# powerAndCommunication.net
KiCad netlist of a schematic drawn in Altium Designer
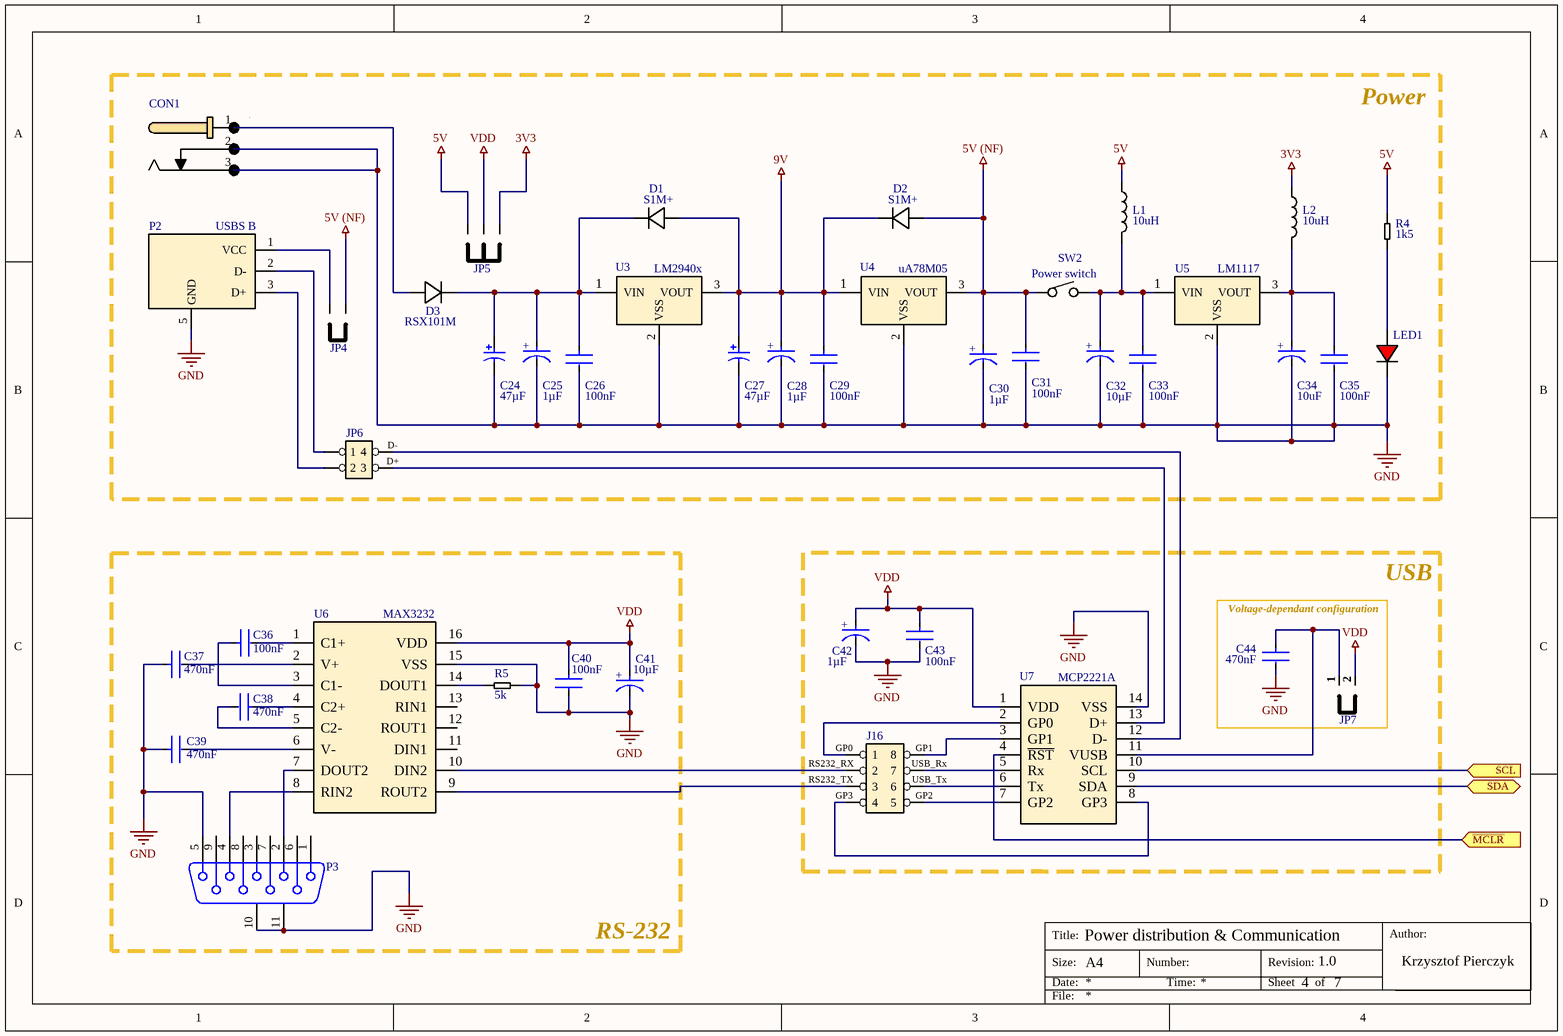
[diagram p0: powerAndCommunication.SchDoc]

(export (version "E")
  (design (tool "Eeschema 10.0.6"))
  (components
    (comp (ref "C24")
      (value "EEE-FK1V331P")
      (footprint "PNSC-EEE-FK1V331P_L")
      (description "Aluminum Electrolytic Capacitor, 330 uF, 35 V, -55 to 105 degC, 2-Pin CAPAE, RoHS, Tape and Reel")
      (fields (field (name "CAPACITANCE") "47µF") (field (name "MANUFACTURER") "Panasonic"))
      (libsource (lib "Altium Content Vault") (part "CAP-P-2"))
    )
    (comp (ref "C25")
      (value "F981C106MSAAS1")
      (footprint "FP-F98S-MFG")
      (description "CAP TANT 10UF 20% 16V 0805")
      (fields
        (field (name "TOLERANCE") "20%")
        (field (name "CAPACITANCE") "1µF")
        (field (name "OCTOPART") "https://octopart.com/f981c106msaas1-avx-49645945")
      )
      (libsource (lib "Altium Content Vault") (part "cf48714ba7e38822c1575c7ec0b6d1f"))
    )
    (comp (ref "C26")
      (value "100nF")
      (footprint "FP-C0805C-DN-MFG")
      (description "CAP CER 1000PF 50V C0G/NP0 0805")
      (fields
        (field (name "MANUFACTURER") "KEMET")
        (field (name "OCTOPART") "https://octopart.com/c0805c102j5gactu-kemet-97757")
      )
      (libsource (lib "Altium Content Vault") (part "b4654b650e69147ec39a6b967a45e02"))
    )
    (comp (ref "C27")
      (value "EEE-FK1V331P")
      (footprint "PNSC-EEE-FK1V331P_L")
      (description "Aluminum Electrolytic Capacitor, 330 uF, 35 V, -55 to 105 degC, 2-Pin CAPAE, RoHS, Tape and Reel")
      (fields (field (name "CAPACITANCE") "47µF") (field (name "MANUFACTURER") "Panasonic"))
      (libsource (lib "Altium Content Vault") (part "CAP-P-2"))
    )
    (comp (ref "C28")
      (value "F981C106MSAAS1")
      (footprint "FP-F98S-MFG")
      (description "CAP TANT 10UF 20% 16V 0805")
      (fields
        (field (name "TOLERANCE") "20%")
        (field (name "CAPACITANCE") "1µF")
        (field (name "OCTOPART") "https://octopart.com/f981c106msaas1-avx-49645945")
      )
      (libsource (lib "Altium Content Vault") (part "cf48714ba7e38822c1575c7ec0b6d1f"))
    )
    (comp (ref "C29")
      (value "100nF")
      (footprint "FP-C0805C-DN-MFG")
      (description "CAP CER 1000PF 50V C0G/NP0 0805")
      (fields
        (field (name "MANUFACTURER") "KEMET")
        (field (name "OCTOPART") "https://octopart.com/c0805c102j5gactu-kemet-97757")
      )
      (libsource (lib "Altium Content Vault") (part "b4654b650e69147ec39a6b967a45e02"))
    )
    (comp (ref "C30")
      (value "F981C106MSAAS1")
      (footprint "FP-F98S-MFG")
      (description "CAP TANT 10UF 20% 16V 0805")
      (fields
        (field (name "TOLERANCE") "20%")
        (field (name "CAPACITANCE") "1µF")
        (field (name "OCTOPART") "https://octopart.com/f981c106msaas1-avx-49645945")
      )
      (libsource (lib "Altium Content Vault") (part "cf48714ba7e38822c1575c7ec0b6d1f"))
    )
    (comp (ref "C31")
      (value "100nF")
      (footprint "FP-C0805C-DN-MFG")
      (description "CAP CER 1000PF 50V C0G/NP0 0805")
      (fields
        (field (name "MANUFACTURER") "KEMET")
        (field (name "OCTOPART") "https://octopart.com/c0805c102j5gactu-kemet-97757")
      )
      (libsource (lib "Altium Content Vault") (part "b4654b650e69147ec39a6b967a45e02"))
    )
    (comp (ref "C32")
      (value "F981C106MSAAS1")
      (footprint "FP-F98S-MFG")
      (description "CAP TANT 10UF 20% 16V 0805")
      (fields
        (field (name "TOLERANCE") "20%")
        (field (name "CAPACITANCE") "10µF")
        (field (name "OCTOPART") "https://octopart.com/f981c106msaas1-avx-49645945")
      )
      (libsource (lib "Altium Content Vault") (part "cf48714ba7e38822c1575c7ec0b6d1f"))
    )
    (comp (ref "C33")
      (value "100nF")
      (footprint "FP-C0805C-DN-MFG")
      (description "CAP CER 1000PF 50V C0G/NP0 0805")
      (fields
        (field (name "MANUFACTURER") "KEMET")
        (field (name "OCTOPART") "https://octopart.com/c0805c102j5gactu-kemet-97757")
      )
      (libsource (lib "Altium Content Vault") (part "b4654b650e69147ec39a6b967a45e02"))
    )
    (comp (ref "C34")
      (value "F981C106MSAAS1")
      (footprint "FP-F98S-MFG")
      (description "CAP TANT 10UF 20% 16V 0805")
      (fields
        (field (name "TOLERANCE") "20%")
        (field (name "CAPACITANCE") "10uF")
        (field (name "OCTOPART") "https://octopart.com/f981c106msaas1-avx-49645945")
      )
      (libsource (lib "Altium Content Vault") (part "cf48714ba7e38822c1575c7ec0b6d1f"))
    )
    (comp (ref "C35")
      (value "100nF")
      (footprint "FP-C0805C-DN-MFG")
      (description "CAP CER 1000PF 50V C0G/NP0 0805")
      (fields
        (field (name "MANUFACTURER") "KEMET")
        (field (name "OCTOPART") "https://octopart.com/c0805c102j5gactu-kemet-97757")
      )
      (libsource (lib "Altium Content Vault") (part "b4654b650e69147ec39a6b967a45e02"))
    )
    (comp (ref "C36")
      (value "100nF")
      (footprint "FP-C0805C-DN-MFG")
      (description "CAP CER 1000PF 50V C0G/NP0 0805")
      (fields
        (field (name "MANUFACTURER") "KEMET")
        (field (name "OCTOPART") "https://octopart.com/c0805c102j5gactu-kemet-97757")
      )
      (libsource (lib "Altium Content Vault") (part "b4654b650e69147ec39a6b967a45e02"))
    )
    (comp (ref "C37")
      (value "470nF")
      (footprint "FP-C0805C-DN-MFG")
      (description "CAP CER 1000PF 50V C0G/NP0 0805")
      (fields
        (field (name "MANUFACTURER") "KEMET")
        (field (name "OCTOPART") "https://octopart.com/c0805c102j5gactu-kemet-97757")
      )
      (libsource (lib "Altium Content Vault") (part "b4654b650e69147ec39a6b967a45e02"))
    )
    (comp (ref "C38")
      (value "470nF")
      (footprint "FP-C0805C-DN-MFG")
      (description "CAP CER 1000PF 50V C0G/NP0 0805")
      (fields
        (field (name "MANUFACTURER") "KEMET")
        (field (name "OCTOPART") "https://octopart.com/c0805c102j5gactu-kemet-97757")
      )
      (libsource (lib "Altium Content Vault") (part "b4654b650e69147ec39a6b967a45e02"))
    )
    (comp (ref "C39")
      (value "470nF")
      (footprint "FP-C0805C-DN-MFG")
      (description "CAP CER 1000PF 50V C0G/NP0 0805")
      (fields
        (field (name "MANUFACTURER") "KEMET")
        (field (name "OCTOPART") "https://octopart.com/c0805c102j5gactu-kemet-97757")
      )
      (libsource (lib "Altium Content Vault") (part "b4654b650e69147ec39a6b967a45e02"))
    )
    (comp (ref "C40")
      (value "100nF")
      (footprint "FP-C0805C-DN-MFG")
      (description "CAP CER 1000PF 50V C0G/NP0 0805")
      (fields
        (field (name "MANUFACTURER") "KEMET")
        (field (name "OCTOPART") "https://octopart.com/c0805c102j5gactu-kemet-97757")
      )
      (libsource (lib "Altium Content Vault") (part "b4654b650e69147ec39a6b967a45e02"))
    )
    (comp (ref "C41")
      (value "F981C106MSAAS1")
      (footprint "FP-F98S-MFG")
      (description "CAP TANT 10UF 20% 16V 0805")
      (fields
        (field (name "TOLERANCE") "20%")
        (field (name "CAPACITANCE") "10µF")
        (field (name "OCTOPART") "https://octopart.com/f981c106msaas1-avx-49645945")
      )
      (libsource (lib "Altium Content Vault") (part "cf48714ba7e38822c1575c7ec0b6d1f"))
    )
    (comp (ref "C42")
      (value "F981C106MSAAS1")
      (footprint "FP-F98S-MFG")
      (description "CAP TANT 10UF 20% 16V 0805")
      (fields
        (field (name "TOLERANCE") "20%")
        (field (name "CAPACITANCE") "1µF")
        (field (name "OCTOPART") "https://octopart.com/f981c106msaas1-avx-49645945")
      )
      (libsource (lib "Altium Content Vault") (part "cf48714ba7e38822c1575c7ec0b6d1f"))
    )
    (comp (ref "C43")
      (value "100nF")
      (footprint "FP-C0805C-DN-MFG")
      (description "CAP CER 1000PF 50V C0G/NP0 0805")
      (fields
        (field (name "MANUFACTURER") "KEMET")
        (field (name "OCTOPART") "https://octopart.com/c0805c102j5gactu-kemet-97757")
      )
      (libsource (lib "Altium Content Vault") (part "b4654b650e69147ec39a6b967a45e02"))
    )
    (comp (ref "C44")
      (value "470nF")
      (footprint "FP-C0805C-DN-MFG")
      (description "CAP CER 1000PF 50V C0G/NP0 0805")
      (fields
        (field (name "MANUFACTURER") "KEMET")
        (field (name "OCTOPART") "https://octopart.com/c0805c102j5gactu-kemet-97757")
      )
      (libsource (lib "Altium Content Vault") (part "b4654b650e69147ec39a6b967a45e02"))
    )
    (comp (ref "CON1")
      (value "FC681477")
      (footprint "FC681477")
      (libsource (lib "miscellanea") (part "DC Jack"))
    )
    (comp (ref "D1")
      (value "S1M+")
      (footprint "SMA")
      (libsource (lib "discrete_semiconductors") (part "S1M+_1"))
    )
    (comp (ref "D2")
      (value "S1M+")
      (footprint "SMA")
      (libsource (lib "discrete_semiconductors") (part "S1M+_1"))
    )
    (comp (ref "D3")
      (value "RSX101M")
      (footprint "SOD-123")
      (libsource (lib "discrete_semiconductors") (part "RSX101M-30TR"))
    )
    (comp (ref "J16")
      (value "Header 2x4")
      (footprint "Header 2x4")
      (libsource (lib "goldpin") (part "Header 2x4"))
    )
    (comp (ref "JP4") (value "JUMPER-2") (footprint "HDR1X2") (libsource (lib "goldpin") (part "JUMPER-2")))
    (comp (ref "JP5") (value "JUMPER-3") (footprint "HDR1X3") (libsource (lib "goldpin") (part "JUMPER-3")))
    (comp (ref "JP6")
      (value "Header 2x2")
      (footprint "Header 2x2")
      (libsource (lib "goldpin") (part "Header 2x2"))
    )
    (comp (ref "JP7") (value "JUMPER-2") (footprint "Header 1x2") (libsource (lib "") (part "JUMPER-2_1")))
    (comp (ref "L1")
      (value "NL05JTC100")
      (footprint "0805")
      (description "SMD coil")
      (fields (field (name "INDUCTANCE") "10uH") (field (name "TOLERANCE") "+/- 20%"))
      (libsource (lib "passive") (part "Coil"))
    )
    (comp (ref "L2")
      (value "NL05JTC100")
      (footprint "0805")
      (description "SMD coil")
      (fields (field (name "INDUCTANCE") "10uH") (field (name "TOLERANCE") "+/- 20%"))
      (libsource (lib "passive") (part "Coil"))
    )
    (comp (ref "LED1")
      (value "Red LED")
      (footprint "LED (0805)")
      (libsource (lib "discrete_semiconductors") (part "Red LED"))
    )
    (comp (ref "P2")
      (value "USBS B")
      (footprint "USB B (female)")
      (libsource (lib "miscellanea") (part "LUMBERG241103"))
    )
    (comp (ref "P3")
      (value "D Connector 9")
      (footprint "DSUB1.385-2H9")
      (description "Receptacle Assembly, 9 Position, Right Angle")
      (fields (field (name "PUBLISHER") "Altium Limited"))
      (libsource (lib "Miscellaneous Connectors") (part "D Connector 9"))
    )
    (comp (ref "R4")
      (value "Resistor")
      (footprint "0805")
      (fields (field (name "RESISTANCE") "1k5"))
      (libsource (lib "passive") (part "Resistor"))
    )
    (comp (ref "R5")
      (value "Resistor")
      (footprint "0805")
      (fields (field (name "RESISTANCE") "5k"))
      (libsource (lib "") (part "Resistor_1"))
    )
    (comp (ref "SW2")
      (value "Power switch")
      (footprint "Switch 4.7mm (botland)")
      (libsource (lib "miscellanea") (part "Double switch"))
    )
    (comp (ref "U3")
      (value "LM2940x")
      (footprint "TO-220 (H)")
      (libsource (lib "integrated") (part "LM2940x"))
    )
    (comp (ref "U4")
      (value "uA78M05")
      (footprint "TO-220 (H)")
      (libsource (lib "integrated") (part "uA78M05"))
    )
    (comp (ref "U5") (value "LM1117") (footprint "TO-220 (H)") (libsource (lib "integrated") (part "LM1117")))
    (comp (ref "U6")
      (value "MAX3232")
      (footprint "SOIC-16 (150mil)")
      (libsource (lib "integrated") (part "MAX3232"))
    )
    (comp (ref "U7")
      (value "MCP2221A")
      (footprint "SOIC-14")
      (libsource (lib "integrated") (part "MCP2221A"))
    )
  )
  (nets
    (net (code "1") (name "/D+") (class "Default")
      (node (ref "JP6") (pin "3") (pinfunction "3_3") (pintype "passive"))
      (node (ref "U7") (pin "13") (pinfunction "D+_13") (pintype "passive"))
    )
    (net (code "2") (name "/D-") (class "Default")
      (node (ref "JP6") (pin "4") (pinfunction "4_4") (pintype "passive"))
      (node (ref "U7") (pin "12") (pinfunction "D-_12") (pintype "passive"))
    )
    (net (code "3") (name "/GP0") (class "Default")
      (node (ref "J16") (pin "1") (pinfunction "1_1") (pintype "passive"))
      (node (ref "U7") (pin "2") (pinfunction "GP0_2") (pintype "passive"))
    )
    (net (code "4") (name "/GP1") (class "Default")
      (node (ref "J16") (pin "8") (pinfunction "8_8") (pintype "passive"))
      (node (ref "U7") (pin "3") (pinfunction "GP1_3") (pintype "passive"))
    )
    (net (code "5") (name "/GP2") (class "Default")
      (node (ref "J16") (pin "5") (pinfunction "5_5") (pintype "passive"))
      (node (ref "U7") (pin "7") (pinfunction "GP2_7") (pintype "passive"))
    )
    (net (code "6") (name "/GP3") (class "Default")
      (node (ref "J16") (pin "4") (pinfunction "4_4") (pintype "passive"))
      (node (ref "U7") (pin "8") (pinfunction "GP3_8") (pintype "passive"))
    )
    (net (code "7") (name "/RS232_RX") (class "Default")
      (node (ref "J16") (pin "2") (pinfunction "2_2") (pintype "passive"))
      (node (ref "U6") (pin "10") (pinfunction "DIN2_10") (pintype "passive"))
    )
    (net (code "8") (name "/RS232_TX") (class "Default")
      (node (ref "J16") (pin "3") (pinfunction "3_3") (pintype "passive"))
      (node (ref "U6") (pin "9") (pinfunction "ROUT2_9") (pintype "passive"))
    )
    (net (code "9") (name "/SCL") (class "Default")
      (node (ref "U7") (pin "10") (pinfunction "SCL_10") (pintype "passive"))
    )
    (net (code "10") (name "/SDA") (class "Default")
      (node (ref "U7") (pin "9") (pinfunction "SDA_9") (pintype "passive"))
    )
    (net (code "11") (name "/USB_Rx") (class "Default")
      (node (ref "J16") (pin "7") (pinfunction "7_7") (pintype "passive"))
      (node (ref "U7") (pin "5") (pinfunction "Rx_5") (pintype "passive"))
    )
    (net (code "12") (name "/USB_Tx") (class "Default")
      (node (ref "J16") (pin "6") (pinfunction "6_6") (pintype "passive"))
      (node (ref "U7") (pin "6") (pinfunction "Tx_6") (pintype "passive"))
    )
    (net (code "13") (name "/~{MCLR}") (class "Default")
      (node (ref "U7") (pin "4") (pinfunction "~{RST}_4") (pintype "passive"))
    )
    (net (code "14") (name "3V3") (class "Default")
      (node (ref "JP5") (pin "3") (pintype "passive"))
      (node (ref "L2") (pin "1") (pintype "passive"))
    )
    (net (code "15") (name "5V") (class "Default")
      (node (ref "JP5") (pin "1") (pintype "passive"))
      (node (ref "L1") (pin "1") (pintype "passive"))
      (node (ref "R4") (pin "1") (pinfunction "1_1") (pintype "passive"))
    )
    (net (code "16") (name "5V (NF)") (class "Default")
      (node (ref "C30") (pin "2") (pinfunction "A_2") (pintype "passive"))
      (node (ref "C31") (pin "1") (pinfunction "1_1") (pintype "passive"))
      (node (ref "D2") (pin "2") (pinfunction "2_2") (pintype "passive"))
      (node (ref "JP4") (pin "2") (pintype "passive"))
      (node (ref "SW2") (pin "2") (pinfunction "COM_2") (pintype "passive"))
      (node (ref "U4") (pin "3") (pinfunction "VOUT_3") (pintype "passive"))
    )
    (net (code "17") (name "9V") (class "Default")
      (node (ref "C27") (pin "1") (pinfunction "1_1") (pintype "passive"))
      (node (ref "C28") (pin "2") (pinfunction "A_2") (pintype "passive"))
      (node (ref "C29") (pin "1") (pinfunction "1_1") (pintype "passive"))
      (node (ref "D1") (pin "2") (pinfunction "2_2") (pintype "passive"))
      (node (ref "D2") (pin "1") (pinfunction "1_1") (pintype "passive"))
      (node (ref "U3") (pin "3") (pinfunction "VOUT_3") (pintype "passive"))
      (node (ref "U4") (pin "1") (pinfunction "VIN_1") (pintype "passive"))
    )
    (net (code "18") (name "GND") (class "Default")
      (node (ref "C24") (pin "2") (pinfunction "2_2") (pintype "passive"))
      (node (ref "C25") (pin "1") (pinfunction "C_1") (pintype "passive"))
      (node (ref "C26") (pin "2") (pinfunction "2_2") (pintype "passive"))
      (node (ref "C27") (pin "2") (pinfunction "2_2") (pintype "passive"))
      (node (ref "C28") (pin "1") (pinfunction "C_1") (pintype "passive"))
      (node (ref "C29") (pin "2") (pinfunction "2_2") (pintype "passive"))
      (node (ref "C30") (pin "1") (pinfunction "C_1") (pintype "passive"))
      (node (ref "C31") (pin "2") (pinfunction "2_2") (pintype "passive"))
      (node (ref "C32") (pin "1") (pinfunction "C_1") (pintype "passive"))
      (node (ref "C33") (pin "2") (pinfunction "2_2") (pintype "passive"))
      (node (ref "C34") (pin "1") (pinfunction "C_1") (pintype "passive"))
      (node (ref "C35") (pin "2") (pinfunction "2_2") (pintype "passive"))
      (node (ref "C37") (pin "1") (pinfunction "1_1") (pintype "passive"))
      (node (ref "C39") (pin "1") (pinfunction "1_1") (pintype "passive"))
      (node (ref "C40") (pin "2") (pinfunction "2_2") (pintype "passive"))
      (node (ref "C41") (pin "1") (pinfunction "C_1") (pintype "passive"))
      (node (ref "C42") (pin "1") (pinfunction "C_1") (pintype "passive"))
      (node (ref "C43") (pin "2") (pinfunction "2_2") (pintype "passive"))
      (node (ref "C44") (pin "2") (pinfunction "2_2") (pintype "passive"))
      (node (ref "CON1") (pin "2") (pintype "passive"))
      (node (ref "CON1") (pin "3") (pintype "passive"))
      (node (ref "LED1") (pin "2") (pinfunction "2_2") (pintype "passive"))
      (node (ref "P2") (pin "5") (pinfunction "GND_5") (pintype "passive"))
      (node (ref "P3") (pin "10") (pinfunction "MH1_10") (pintype "passive"))
      (node (ref "P3") (pin "11") (pinfunction "MH2_11") (pintype "passive"))
      (node (ref "P3") (pin "5") (pinfunction "5_5") (pintype "passive"))
      (node (ref "R5") (pin "2") (pinfunction "2_2") (pintype "passive"))
      (node (ref "U3") (pin "2") (pinfunction "VSS_2") (pintype "passive"))
      (node (ref "U4") (pin "2") (pinfunction "VSS_2") (pintype "passive"))
      (node (ref "U5") (pin "2") (pinfunction "VSS_2") (pintype "passive"))
      (node (ref "U6") (pin "15") (pinfunction "VSS_15") (pintype "passive"))
      (node (ref "U7") (pin "14") (pinfunction "VSS_14") (pintype "passive"))
    )
    (net (code "19") (name "Net-(C25-A)") (class "Default")
      (node (ref "C24") (pin "1") (pinfunction "1_1") (pintype "passive"))
      (node (ref "C25") (pin "2") (pinfunction "A_2") (pintype "passive"))
      (node (ref "C26") (pin "1") (pinfunction "1_1") (pintype "passive"))
      (node (ref "D1") (pin "1") (pinfunction "1_1") (pintype "passive"))
      (node (ref "D3") (pin "2") (pinfunction "2_2") (pintype "passive"))
      (node (ref "U3") (pin "1") (pinfunction "VIN_1") (pintype "passive"))
    )
    (net (code "20") (name "Net-(C32-A)") (class "Default")
      (node (ref "C32") (pin "2") (pinfunction "A_2") (pintype "passive"))
      (node (ref "C33") (pin "1") (pinfunction "1_1") (pintype "passive"))
      (node (ref "L1") (pin "2") (pintype "passive"))
      (node (ref "SW2") (pin "1") (pinfunction "1_1") (pintype "passive"))
      (node (ref "U5") (pin "1") (pinfunction "VIN_1") (pintype "passive"))
    )
    (net (code "21") (name "Net-(C34-A)") (class "Default")
      (node (ref "C34") (pin "2") (pinfunction "A_2") (pintype "passive"))
      (node (ref "C35") (pin "1") (pinfunction "1_1") (pintype "passive"))
      (node (ref "L2") (pin "2") (pintype "passive"))
      (node (ref "U5") (pin "3") (pinfunction "VOUT_3") (pintype "passive"))
    )
    (net (code "22") (name "Net-(CON1-Pad1)") (class "Default")
      (node (ref "CON1") (pin "1") (pintype "passive"))
      (node (ref "D3") (pin "1") (pinfunction "1_1") (pintype "passive"))
    )
    (net (code "23") (name "Net-(LED1-Pad1)") (class "Default")
      (node (ref "LED1") (pin "1") (pinfunction "1_1") (pintype "passive"))
      (node (ref "R4") (pin "2") (pinfunction "2_2") (pintype "passive"))
    )
    (net (code "24") (name "Net-(P2-D+)") (class "Default")
      (node (ref "JP6") (pin "2") (pinfunction "2_2") (pintype "passive"))
      (node (ref "P2") (pin "3") (pinfunction "D+_3") (pintype "passive"))
    )
    (net (code "25") (name "Net-(P2-D-)") (class "Default")
      (node (ref "JP6") (pin "1") (pinfunction "1_1") (pintype "passive"))
      (node (ref "P2") (pin "2") (pinfunction "D-_2") (pintype "passive"))
    )
    (net (code "26") (name "Net-(P2-VCC)") (class "Default")
      (node (ref "JP4") (pin "1") (pintype "passive"))
      (node (ref "P2") (pin "1") (pinfunction "VCC_1") (pintype "passive"))
    )
    (net (code "27") (name "Net-(U6-C1+)") (class "Default")
      (node (ref "C36") (pin "2") (pinfunction "2_2") (pintype "passive"))
      (node (ref "U6") (pin "1") (pinfunction "C1+_1") (pintype "passive"))
    )
    (net (code "28") (name "Net-(U6-C1-)") (class "Default")
      (node (ref "C36") (pin "1") (pinfunction "1_1") (pintype "passive"))
      (node (ref "U6") (pin "3") (pinfunction "C1-_3") (pintype "passive"))
    )
    (net (code "29") (name "Net-(U6-C2+)") (class "Default")
      (node (ref "C38") (pin "1") (pinfunction "1_1") (pintype "passive"))
      (node (ref "U6") (pin "4") (pinfunction "C2+_4") (pintype "passive"))
    )
    (net (code "30") (name "Net-(U6-C2-)") (class "Default")
      (node (ref "C38") (pin "2") (pinfunction "2_2") (pintype "passive"))
      (node (ref "U6") (pin "5") (pinfunction "C2-_5") (pintype "passive"))
    )
    (net (code "31") (name "Net-(U6-DOUT1)") (class "Default")
      (node (ref "R5") (pin "1") (pinfunction "1_1") (pintype "passive"))
      (node (ref "U6") (pin "14") (pinfunction "DOUT1_14") (pintype "passive"))
    )
    (net (code "32") (name "Net-(U6-DOUT2)") (class "Default")
      (node (ref "P3") (pin "2") (pinfunction "2_2") (pintype "passive"))
      (node (ref "U6") (pin "7") (pinfunction "DOUT2_7") (pintype "passive"))
    )
    (net (code "33") (name "Net-(U6-RIN2)") (class "Default")
      (node (ref "P3") (pin "4") (pinfunction "4_4") (pintype "passive"))
      (node (ref "U6") (pin "8") (pinfunction "RIN2_8") (pintype "passive"))
    )
    (net (code "34") (name "Net-(U6-V+)") (class "Default")
      (node (ref "C37") (pin "2") (pinfunction "2_2") (pintype "passive"))
      (node (ref "U6") (pin "2") (pinfunction "V+_2") (pintype "passive"))
    )
    (net (code "35") (name "Net-(U6-V-)") (class "Default")
      (node (ref "C39") (pin "2") (pinfunction "2_2") (pintype "passive"))
      (node (ref "U6") (pin "6") (pinfunction "V-_6") (pintype "passive"))
    )
    (net (code "36") (name "Net-(U7-VUSB)") (class "Default")
      (node (ref "C44") (pin "1") (pinfunction "1_1") (pintype "passive"))
      (node (ref "JP7") (pin "1") (pintype "passive"))
      (node (ref "U7") (pin "11") (pinfunction "VUSB_11") (pintype "passive"))
    )
    (net (code "37") (name "VDD") (class "Default")
      (node (ref "C40") (pin "1") (pinfunction "1_1") (pintype "passive"))
      (node (ref "C41") (pin "2") (pinfunction "A_2") (pintype "passive"))
      (node (ref "C42") (pin "2") (pinfunction "A_2") (pintype "passive"))
      (node (ref "C43") (pin "1") (pinfunction "1_1") (pintype "passive"))
      (node (ref "JP5") (pin "2") (pintype "passive"))
      (node (ref "JP7") (pin "2") (pintype "passive"))
      (node (ref "U6") (pin "16") (pinfunction "VDD_16") (pintype "passive"))
      (node (ref "U7") (pin "1") (pinfunction "VDD_1") (pintype "passive"))
    )
    (net (code "38") (name "unconnected-(P3-Pad1)") (class "Default")
      (node (ref "P3") (pin "1") (pinfunction "1_1") (pintype "passive"))
    )
    (net (code "39") (name "unconnected-(P3-Pad3)") (class "Default")
      (node (ref "P3") (pin "3") (pinfunction "3_3") (pintype "passive"))
    )
    (net (code "40") (name "unconnected-(P3-Pad6)") (class "Default")
      (node (ref "P3") (pin "6") (pinfunction "6_6") (pintype "passive"))
    )
    (net (code "41") (name "unconnected-(P3-Pad7)") (class "Default")
      (node (ref "P3") (pin "7") (pinfunction "7_7") (pintype "passive"))
    )
    (net (code "42") (name "unconnected-(P3-Pad8)") (class "Default")
      (node (ref "P3") (pin "8") (pinfunction "8_8") (pintype "passive"))
    )
    (net (code "43") (name "unconnected-(P3-Pad9)") (class "Default")
      (node (ref "P3") (pin "9") (pinfunction "9_9") (pintype "passive"))
    )
    (net (code "44") (name "unconnected-(U6-DIN1-Pad11)") (class "Default")
      (node (ref "U6") (pin "11") (pinfunction "DIN1_11") (pintype "passive"))
    )
    (net (code "45") (name "unconnected-(U6-RIN1-Pad13)") (class "Default")
      (node (ref "U6") (pin "13") (pinfunction "RIN1_13") (pintype "passive"))
    )
    (net (code "46") (name "unconnected-(U6-ROUT1-Pad12)") (class "Default")
      (node (ref "U6") (pin "12") (pinfunction "ROUT1_12") (pintype "passive"))
    )
  )
)
